# MCP4725_v14.net
KiCad netlist of a schematic drawn in EAGLE
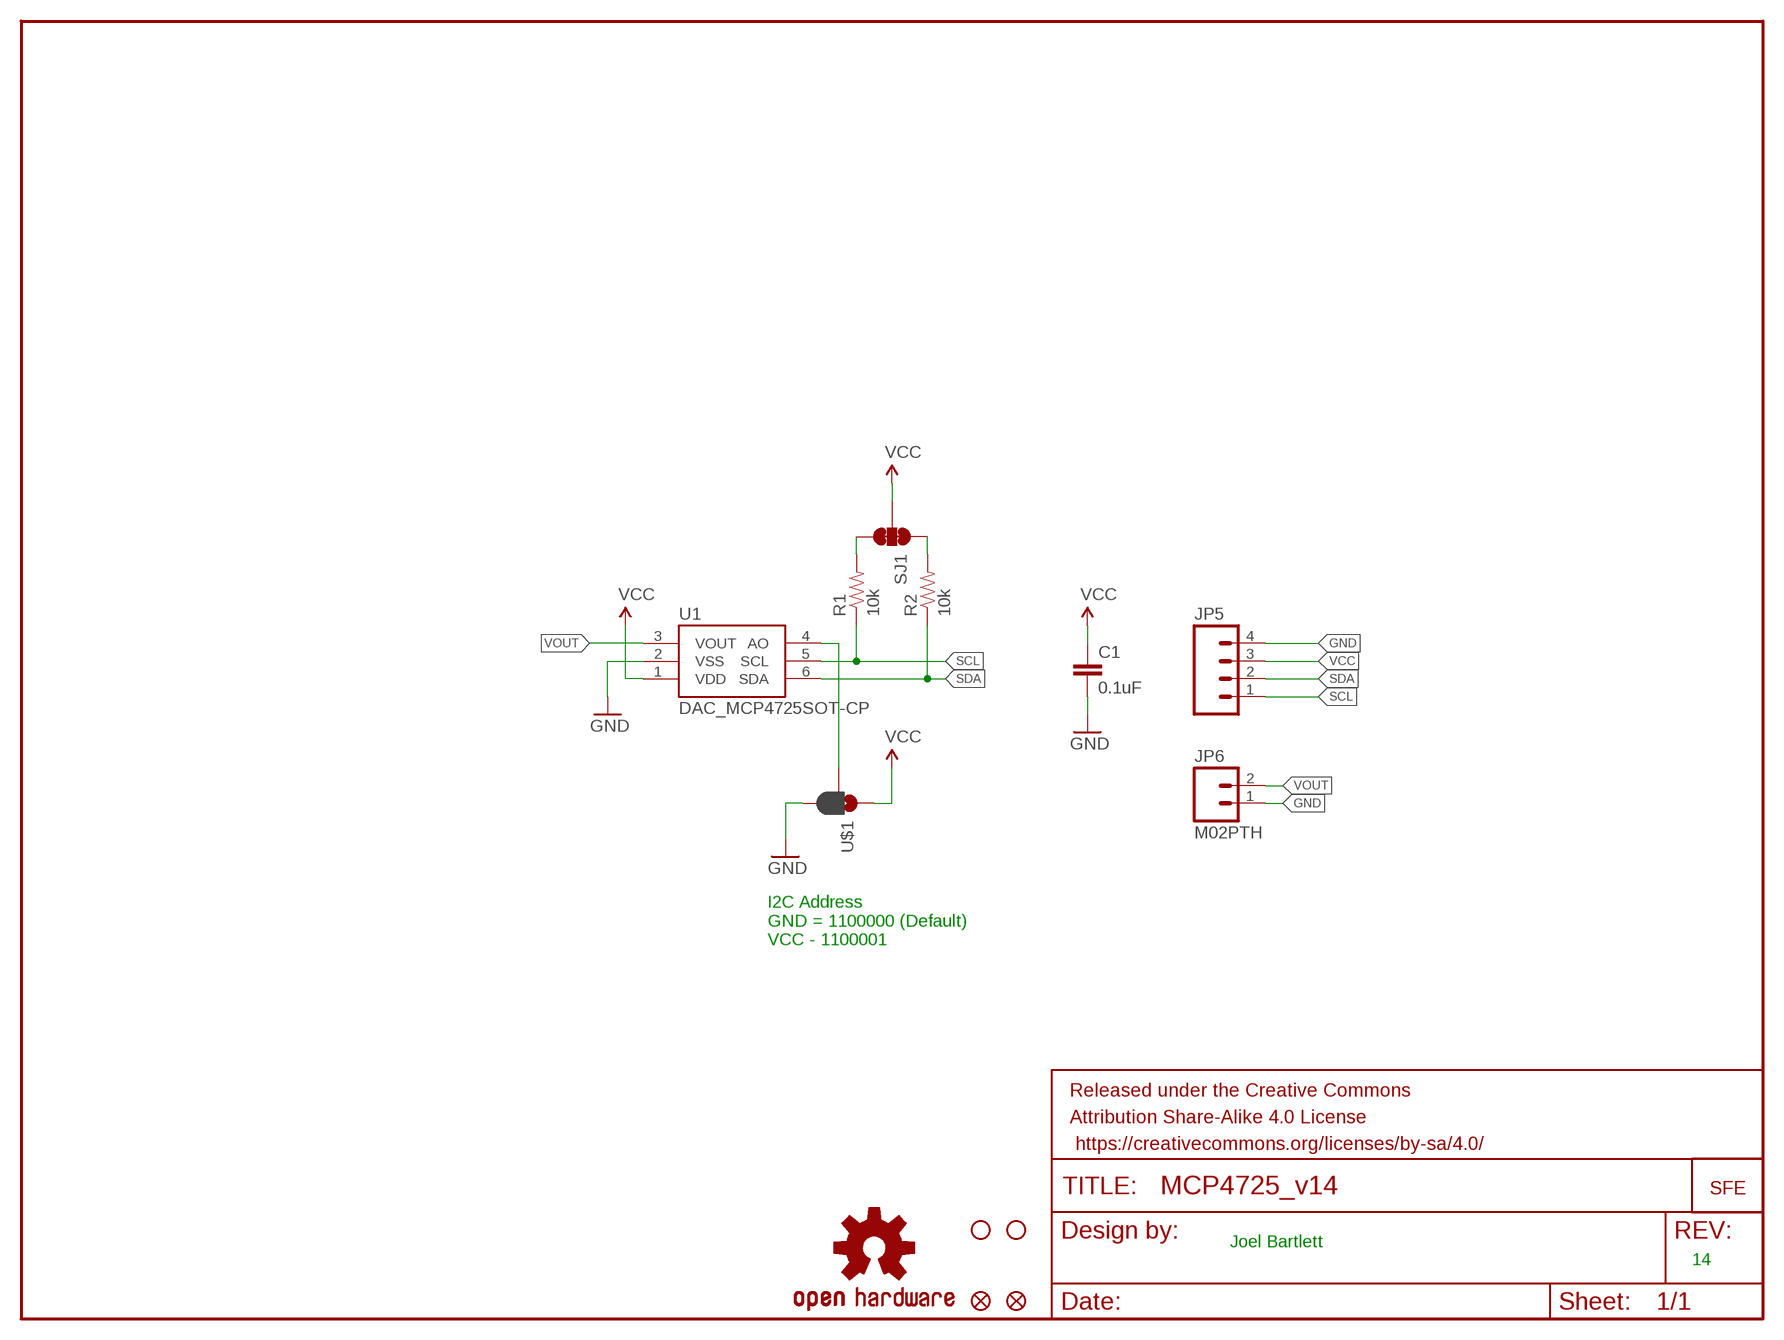
[diagram p0: schematic, sheet 1]

(export (version "E")
  (design (tool "Eeschema 10.0.6"))
  (components
    (comp (ref "C1")
      (value "0.1uF")
      (footprint "eagle-import:0603-CAP")
      (libsource (lib "eagle-import") (part "CAP0603-CAP"))
    )
    (comp (ref "FRAME2")
      (value "FRAME-LETTER")
      (footprint "eagle-import:CREATIVE_COMMONS")
      (libsource (lib "eagle-import") (part "FRAME-LETTER"))
    )
    (comp (ref "GND")
      (value "LOGO-SFESK")
      (footprint "eagle-import:SFE-LOGO-FLAME")
      (libsource (lib "eagle-import") (part "LOGO-SFESK"))
    )
    (comp (ref "JP2")
      (value "FIDUCIALUFIDUCIAL")
      (footprint "eagle-import:MICRO-FIDUCIAL")
      (libsource (lib "eagle-import") (part "FIDUCIALUFIDUCIAL"))
    )
    (comp (ref "JP3")
      (value "FIDUCIALUFIDUCIAL")
      (footprint "eagle-import:MICRO-FIDUCIAL")
      (libsource (lib "eagle-import") (part "FIDUCIALUFIDUCIAL"))
    )
    (comp (ref "JP5")
      (value "M04PTH")
      (footprint "eagle-import:1X04")
      (libsource (lib "eagle-import") (part "M04PTH"))
    )
    (comp (ref "JP6")
      (value "M02PTH")
      (footprint "eagle-import:1X02")
      (libsource (lib "eagle-import") (part "M02PTH"))
    )
    (comp (ref "LOGO1")
      (value "OSHW-LOGOS")
      (footprint "eagle-import:OSHW-LOGO-S")
      (libsource (lib "eagle-import") (part "OSHW-LOGOS"))
    )
    (comp (ref "R1")
      (value "10k")
      (footprint "eagle-import:0603-RES")
      (libsource (lib "eagle-import") (part "RESISTOR0603-RES"))
    )
    (comp (ref "R2")
      (value "10k")
      (footprint "eagle-import:0603-RES")
      (libsource (lib "eagle-import") (part "RESISTOR0603-RES"))
    )
    (comp (ref "SJ1")
      (value "JUMPER-PAD-3-NC_BY_TRACE")
      (footprint "eagle-import:PAD-JUMPER-3-3OF3_NC_BY_TRACE_YES_SILK_FULL_BOX")
      (libsource (lib "eagle-import") (part "JUMPER-PAD-3-NC_BY_TRACE"))
    )
    (comp (ref "STANDOFF1")
      (value "STAND-OFF")
      (footprint "eagle-import:STAND-OFF")
      (libsource (lib "eagle-import") (part "STAND-OFF"))
    )
    (comp (ref "STANDOFF2")
      (value "STAND-OFF")
      (footprint "eagle-import:STAND-OFF")
      (libsource (lib "eagle-import") (part "STAND-OFF"))
    )
    (comp (ref "U$1")
      (value "JUMPER-PAD-3-2OF3_NC_BY_PASTE")
      (footprint "eagle-import:PAD-JUMPER-3-2OF3_NC_BY_PASTE_YES_SILK_FULL_BOX")
      (libsource (lib "eagle-import") (part "JUMPER-PAD-3-2OF3_NC_BY_PASTE"))
    )
    (comp (ref "U1")
      (value "DAC_MCP4725SOT-CP")
      (footprint "eagle-import:SOT23-6-MCP4725")
      (libsource (lib "eagle-import") (part "DAC_MCP4725SOT-CP"))
    )
  )
  (nets
    (net (code "1") (name "GND") (class "Default")
      (node (ref "C1") (pin "2") (pinfunction "2_2") (pintype "passive"))
      (node (ref "JP5") (pin "4") (pinfunction "4_4") (pintype "passive"))
      (node (ref "JP6") (pin "1") (pinfunction "1_1") (pintype "passive"))
      (node (ref "U$1") (pin "3") (pinfunction "3_3") (pintype "passive"))
      (node (ref "U1") (pin "2") (pinfunction "VSS_2") (pintype "bidirectional"))
    )
    (net (code "2") (name "Net-(R1-Pad2)") (class "Default")
      (node (ref "R1") (pin "2") (pinfunction "2_2") (pintype "passive"))
      (node (ref "SJ1") (pin "3") (pinfunction "3_3") (pintype "passive"))
    )
    (net (code "3") (name "Net-(R2-Pad2)") (class "Default")
      (node (ref "R2") (pin "2") (pinfunction "2_2") (pintype "passive"))
      (node (ref "SJ1") (pin "1") (pinfunction "1_1") (pintype "passive"))
    )
    (net (code "4") (name "Net-(U1-AO)") (class "Default")
      (node (ref "U$1") (pin "2") (pinfunction "2_2") (pintype "passive"))
      (node (ref "U1") (pin "4") (pinfunction "AO_4") (pintype "bidirectional"))
    )
    (net (code "5") (name "SCL") (class "Default")
      (node (ref "JP5") (pin "1") (pinfunction "1_1") (pintype "passive"))
      (node (ref "R1") (pin "1") (pinfunction "1_1") (pintype "passive"))
      (node (ref "U1") (pin "5") (pinfunction "SCL_5") (pintype "bidirectional"))
    )
    (net (code "6") (name "SDA") (class "Default")
      (node (ref "JP5") (pin "2") (pinfunction "2_2") (pintype "passive"))
      (node (ref "R2") (pin "1") (pinfunction "1_1") (pintype "passive"))
      (node (ref "U1") (pin "6") (pinfunction "SDA_6") (pintype "bidirectional"))
    )
    (net (code "7") (name "VCC") (class "Default")
      (node (ref "C1") (pin "1") (pinfunction "1_1") (pintype "passive"))
      (node (ref "JP5") (pin "3") (pinfunction "3_3") (pintype "passive"))
      (node (ref "SJ1") (pin "2") (pinfunction "2_2") (pintype "passive"))
      (node (ref "U$1") (pin "1") (pinfunction "1_1") (pintype "passive"))
      (node (ref "U1") (pin "1") (pinfunction "VDD_1") (pintype "bidirectional"))
    )
    (net (code "8") (name "VOUT") (class "Default")
      (node (ref "JP6") (pin "2") (pinfunction "2_2") (pintype "passive"))
      (node (ref "U1") (pin "3") (pinfunction "VOUT_3") (pintype "bidirectional"))
    )
  )
)
